# Infrared_Reception_Sch.net
KiCad netlist of a schematic drawn in Altium Designer
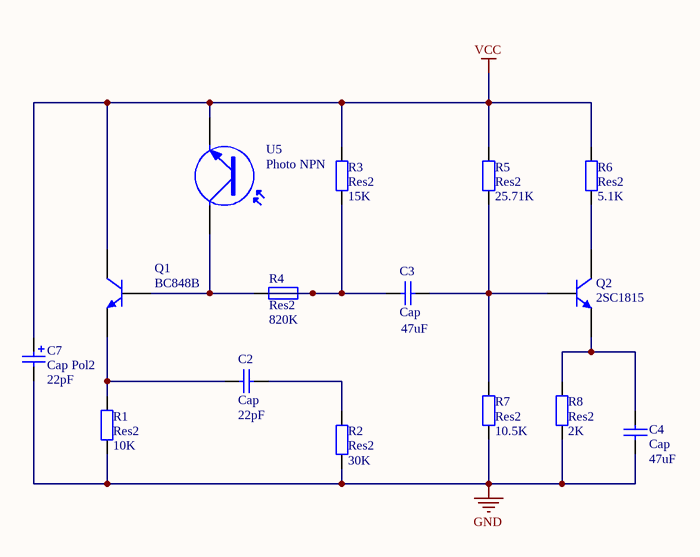
[diagram p0: Infrared Reception_Sch.SchDoc]

(export (version "E")
  (design (tool "Eeschema 10.0.6"))
  (components
    (comp (ref "C2")
      (value "Cap")
      (footprint "RAD-0.3")
      (description "Capacitor")
      (fields (field (name "ALTIUM_VALUE") "22pF") (field (name "PUBLISHER") "Altium Limited"))
      (libsource (lib "Miscellaneous Devices") (part "Cap"))
    )
    (comp (ref "C3")
      (value "Cap")
      (footprint "RAD-0.3")
      (description "Capacitor")
      (fields (field (name "ALTIUM_VALUE") "47uF") (field (name "PUBLISHER") "Altium Limited"))
      (libsource (lib "Miscellaneous Devices") (part "Cap"))
    )
    (comp (ref "C4")
      (value "Cap")
      (footprint "RAD-0.3")
      (description "Capacitor")
      (fields (field (name "ALTIUM_VALUE") "47uF") (field (name "PUBLISHER") "Altium Limited"))
      (libsource (lib "Miscellaneous Devices") (part "Cap"))
    )
    (comp (ref "C7")
      (value "Cap Pol2")
      (footprint "POLAR0.8")
      (description "Polarized Capacitor (Axial)")
      (fields (field (name "ALTIUM_VALUE") "22pF") (field (name "PUBLISHER") "Altium Limited"))
      (libsource (lib "Miscellaneous Devices") (part "Cap Pol2"))
    )
    (comp (ref "Q1")
      (value "BC848B")
      (footprint "TO-92A")
      (description "NPN General Purpose Amplifier")
      (fields (field (name "PUBLISHER") "Altium Limited"))
      (libsource (lib "Miscellaneous Devices") (part "2N3904"))
    )
    (comp (ref "Q2")
      (value "2SC1815")
      (footprint "TO-92A")
      (description "NPN General Purpose Amplifier")
      (fields (field (name "PUBLISHER") "Altium Limited"))
      (libsource (lib "Miscellaneous Devices") (part "2N3904"))
    )
    (comp (ref "R1")
      (value "Res2")
      (footprint "AXIAL-0.4")
      (description "Resistor")
      (fields (field (name "ALTIUM_VALUE") "10K") (field (name "PUBLISHER") "Altium Limited"))
      (libsource (lib "") (part "Res2_1"))
    )
    (comp (ref "R2")
      (value "Res2")
      (footprint "AXIAL-0.4")
      (description "Resistor")
      (fields (field (name "ALTIUM_VALUE") "30K") (field (name "PUBLISHER") "Altium Limited"))
      (libsource (lib "") (part "Res2_1"))
    )
    (comp (ref "R3")
      (value "Res2")
      (footprint "AXIAL-0.4")
      (description "Resistor")
      (fields (field (name "ALTIUM_VALUE") "15K") (field (name "PUBLISHER") "Altium Limited"))
      (libsource (lib "") (part "Res2_1"))
    )
    (comp (ref "R4")
      (value "Res2")
      (footprint "AXIAL-0.4")
      (description "Resistor")
      (fields (field (name "ALTIUM_VALUE") "820K") (field (name "PUBLISHER") "Altium Limited"))
      (libsource (lib "Miscellaneous Devices") (part "Res2"))
    )
    (comp (ref "R5")
      (value "Res2")
      (footprint "AXIAL-0.4")
      (description "Resistor")
      (fields (field (name "ALTIUM_VALUE") "25.71K") (field (name "PUBLISHER") "Altium Limited"))
      (libsource (lib "") (part "Res2_1"))
    )
    (comp (ref "R6")
      (value "Res2")
      (footprint "AXIAL-0.4")
      (description "Resistor")
      (fields (field (name "ALTIUM_VALUE") "5.1K") (field (name "PUBLISHER") "Altium Limited"))
      (libsource (lib "") (part "Res2_1"))
    )
    (comp (ref "R7")
      (value "Res2")
      (footprint "AXIAL-0.4")
      (description "Resistor")
      (fields (field (name "ALTIUM_VALUE") "10.5K") (field (name "PUBLISHER") "Altium Limited"))
      (libsource (lib "") (part "Res2_1"))
    )
    (comp (ref "R8")
      (value "Res2")
      (footprint "AXIAL-0.4")
      (description "Resistor")
      (fields (field (name "ALTIUM_VALUE") "2K") (field (name "PUBLISHER") "Altium Limited"))
      (libsource (lib "") (part "Res2_1"))
    )
    (comp (ref "U5")
      (value "Photo NPN")
      (footprint "TO-220_A")
      (description "NPN Phototransistor")
      (fields (field (name "PUBLISHER") "Altium Limited"))
      (libsource (lib "Miscellaneous Devices") (part "Photo NPN"))
    )
  )
  (nets
    (net (code "1") (name "GND") (class "Default")
      (node (ref "C4") (pin "1") (pinfunction "1_1") (pintype "passive"))
      (node (ref "C7") (pin "2") (pinfunction "2_2") (pintype "passive"))
      (node (ref "R1") (pin "1") (pinfunction "1_1") (pintype "passive"))
      (node (ref "R2") (pin "1") (pinfunction "1_1") (pintype "passive"))
      (node (ref "R7") (pin "1") (pinfunction "1_1") (pintype "passive"))
      (node (ref "R8") (pin "1") (pinfunction "1_1") (pintype "passive"))
    )
    (net (code "2") (name "Net-(C2-Pad2)") (class "Default")
      (node (ref "C2") (pin "2") (pinfunction "2_2") (pintype "passive"))
      (node (ref "R2") (pin "2") (pinfunction "2_2") (pintype "passive"))
    )
    (net (code "3") (name "Net-(C3-Pad1)") (class "Default")
      (node (ref "C3") (pin "1") (pinfunction "1_1") (pintype "passive"))
      (node (ref "R3") (pin "1") (pinfunction "1_1") (pintype "passive"))
      (node (ref "R4") (pin "1") (pinfunction "1_1") (pintype "passive"))
    )
    (net (code "4") (name "Net-(Q1-B)") (class "Default")
      (node (ref "Q1") (pin "2") (pinfunction "B_2") (pintype "passive"))
      (node (ref "R4") (pin "2") (pinfunction "2_2") (pintype "passive"))
      (node (ref "U5") (pin "1") (pinfunction "C_1") (pintype "passive"))
    )
    (net (code "5") (name "Net-(Q1-E)") (class "Default")
      (node (ref "C2") (pin "1") (pinfunction "1_1") (pintype "passive"))
      (node (ref "Q1") (pin "1") (pinfunction "E_1") (pintype "passive"))
      (node (ref "R1") (pin "2") (pinfunction "2_2") (pintype "passive"))
    )
    (net (code "6") (name "Net-(Q2-B)") (class "Default")
      (node (ref "C3") (pin "2") (pinfunction "2_2") (pintype "passive"))
      (node (ref "Q2") (pin "2") (pinfunction "B_2") (pintype "passive"))
      (node (ref "R5") (pin "1") (pinfunction "1_1") (pintype "passive"))
      (node (ref "R7") (pin "2") (pinfunction "2_2") (pintype "passive"))
    )
    (net (code "7") (name "Net-(Q2-C)") (class "Default")
      (node (ref "Q2") (pin "3") (pinfunction "C_3") (pintype "passive"))
      (node (ref "R6") (pin "1") (pinfunction "1_1") (pintype "passive"))
    )
    (net (code "8") (name "Net-(Q2-E)") (class "Default")
      (node (ref "C4") (pin "2") (pinfunction "2_2") (pintype "passive"))
      (node (ref "Q2") (pin "1") (pinfunction "E_1") (pintype "passive"))
      (node (ref "R8") (pin "2") (pinfunction "2_2") (pintype "passive"))
    )
    (net (code "9") (name "VCC") (class "Default")
      (node (ref "C7") (pin "1") (pinfunction "1_1") (pintype "passive"))
      (node (ref "Q1") (pin "3") (pinfunction "C_3") (pintype "passive"))
      (node (ref "R3") (pin "2") (pinfunction "2_2") (pintype "passive"))
      (node (ref "R5") (pin "2") (pinfunction "2_2") (pintype "passive"))
      (node (ref "R6") (pin "2") (pinfunction "2_2") (pintype "passive"))
      (node (ref "U5") (pin "3") (pinfunction "E_3") (pintype "passive"))
    )
  )
)
